# ZoomFloppy_v1_0a.net
KiCad netlist of a schematic drawn in EAGLE
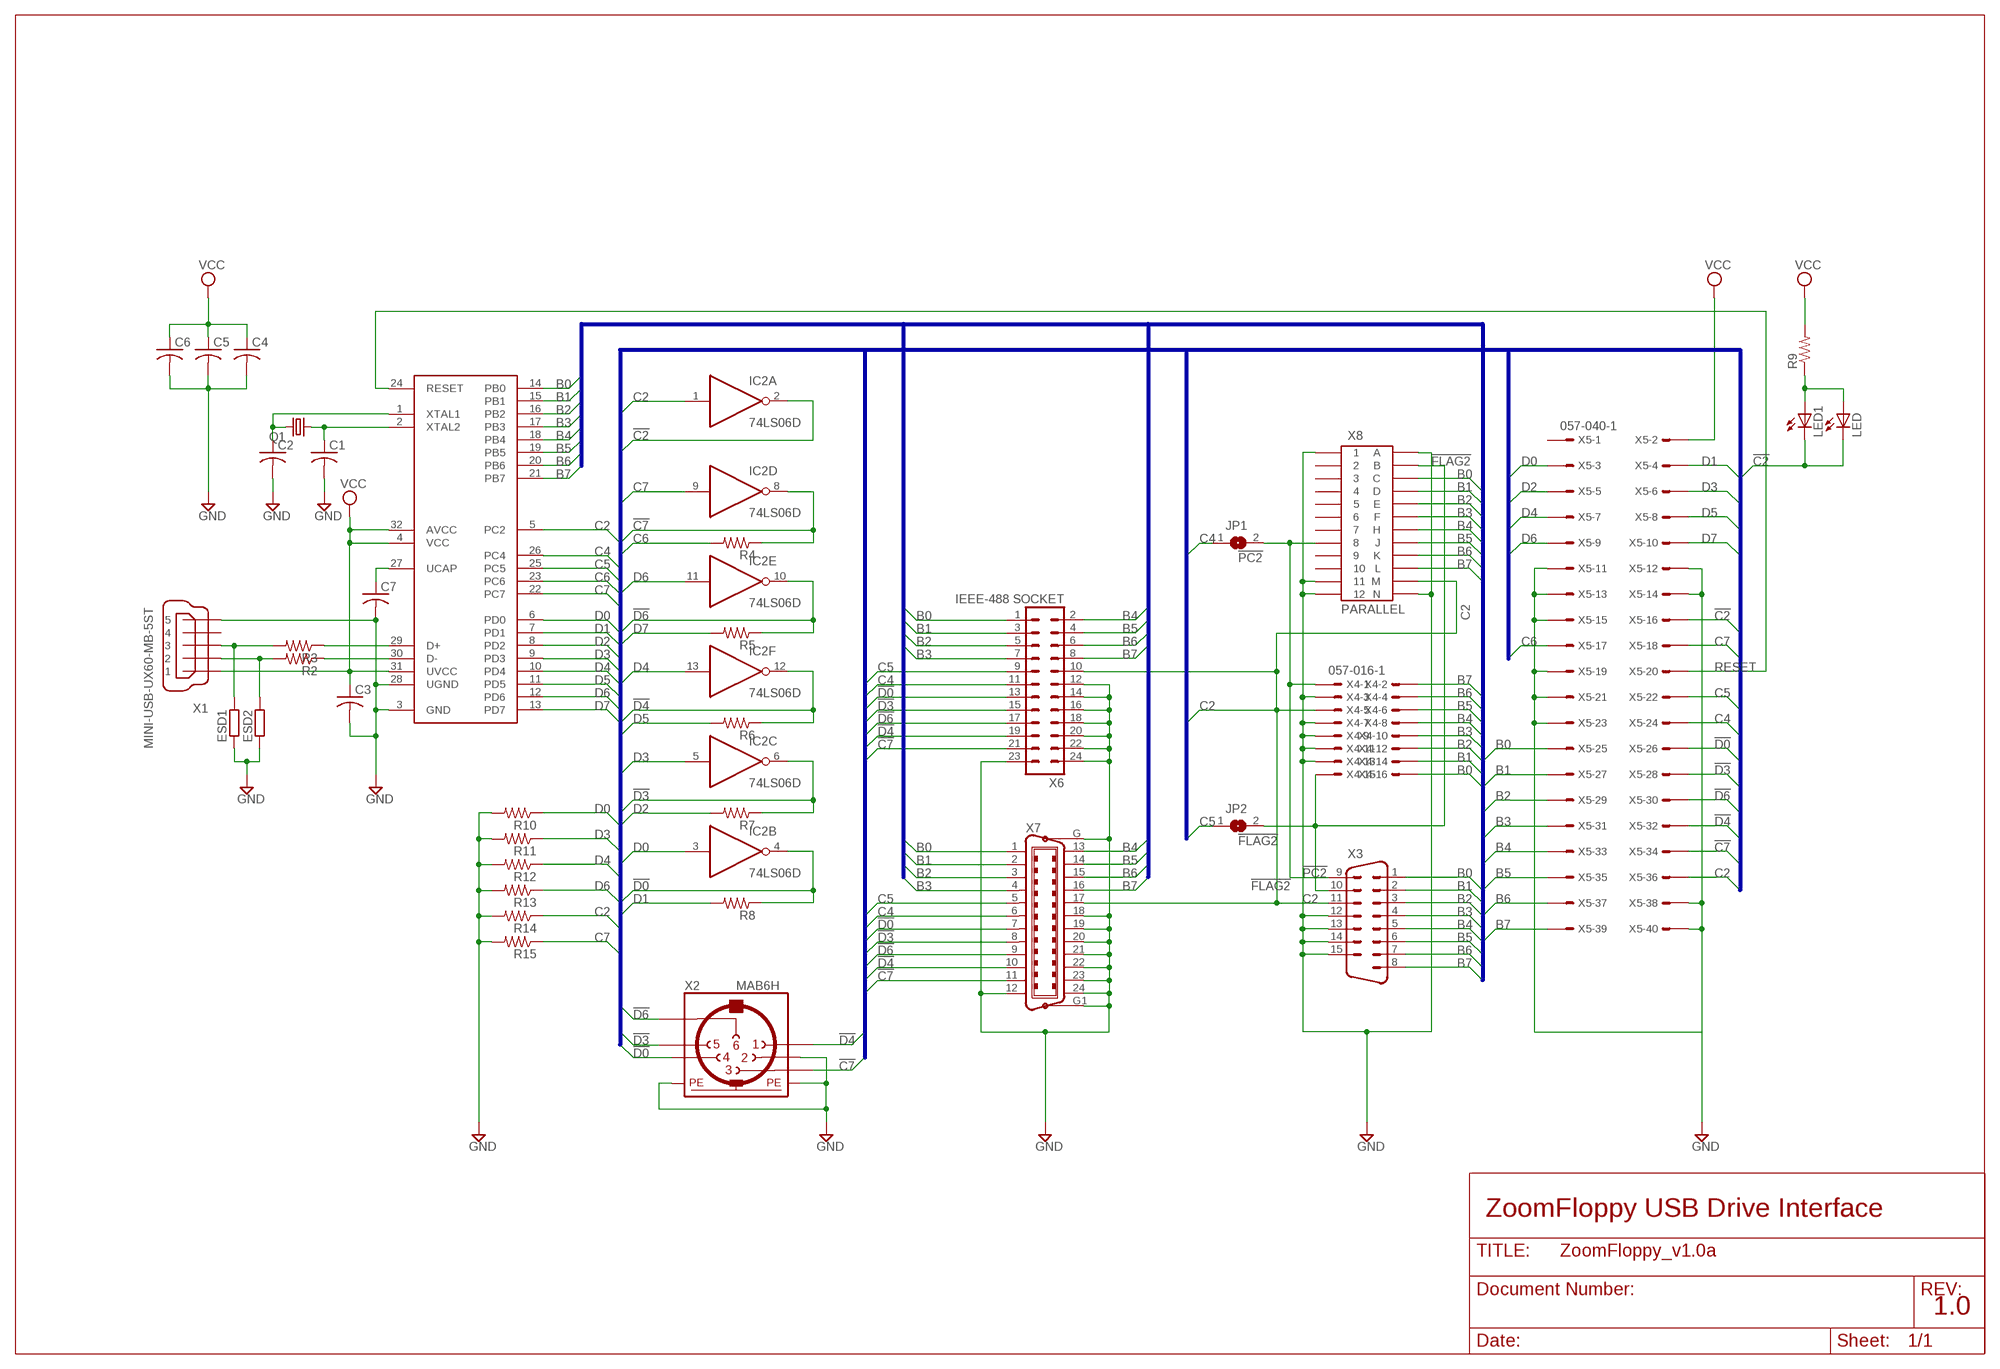
[diagram p0: schematic, sheet 1]

(export (version "E")
  (design (tool "Eeschema 10.0.6"))
  (components
    (comp (ref "C1")
      (value "C-USC0402")
      (footprint "eagle-import:C0402")
      (libsource (lib "eagle-import") (part "C-USC0402"))
    )
    (comp (ref "C2")
      (value "C-USC0402")
      (footprint "eagle-import:C0402")
      (libsource (lib "eagle-import") (part "C-USC0402"))
    )
    (comp (ref "C3")
      (value "C-USC0402")
      (footprint "eagle-import:C0402")
      (libsource (lib "eagle-import") (part "C-USC0402"))
    )
    (comp (ref "C4")
      (value "C-USC0402")
      (footprint "eagle-import:C0402")
      (libsource (lib "eagle-import") (part "C-USC0402"))
    )
    (comp (ref "C5")
      (value "C-USC0402")
      (footprint "eagle-import:C0402")
      (libsource (lib "eagle-import") (part "C-USC0402"))
    )
    (comp (ref "C6")
      (value "C-USC0402")
      (footprint "eagle-import:C0402")
      (libsource (lib "eagle-import") (part "C-USC0402"))
    )
    (comp (ref "C7")
      (value "C-USC0402")
      (footprint "eagle-import:C0402")
      (libsource (lib "eagle-import") (part "C-USC0402"))
    )
    (comp (ref "ESD1")
      (value "R-EU_R0603")
      (footprint "eagle-import:R0603")
      (libsource (lib "eagle-import") (part "R-EU_R0603"))
    )
    (comp (ref "ESD2")
      (value "R-EU_R0603")
      (footprint "eagle-import:R0603")
      (libsource (lib "eagle-import") (part "R-EU_R0603"))
    )
    (comp (ref "IC1")
      (value "ATMEGA32U2")
      (footprint "eagle-import:VQFP32")
      (libsource (lib "eagle-import") (part "AT90USB162"))
    )
    (comp (ref "IC2")
      (value "74LS06D")
      (footprint "eagle-import:SO14")
      (libsource (lib "eagle-import") (part "7406DLS"))
    )
    (comp (ref "JP1") (value "SJ") (footprint "eagle-import:SJ") (libsource (lib "eagle-import") (part "SJ")))
    (comp (ref "JP2") (value "SJ") (footprint "eagle-import:SJ") (libsource (lib "eagle-import") (part "SJ")))
    (comp (ref "LED")
      (value "LED3MM")
      (footprint "eagle-import:LED3MM")
      (libsource (lib "eagle-import") (part "LED3MM"))
    )
    (comp (ref "LED1")
      (value "LEDCHIP-LED0805")
      (footprint "eagle-import:CHIP-LED0805")
      (libsource (lib "eagle-import") (part "LEDCHIP-LED0805"))
    )
    (comp (ref "Q1")
      (value "CRYSTALHC49UP")
      (footprint "eagle-import:HC49UP")
      (libsource (lib "eagle-import") (part "CRYSTALHC49UP"))
    )
    (comp (ref "R2")
      (value "R-US_R0402")
      (footprint "eagle-import:R0402")
      (libsource (lib "eagle-import") (part "R-US_R0402"))
    )
    (comp (ref "R3")
      (value "R-US_R0402")
      (footprint "eagle-import:R0402")
      (libsource (lib "eagle-import") (part "R-US_R0402"))
    )
    (comp (ref "R4")
      (value "R-US_R0402")
      (footprint "eagle-import:R0402")
      (libsource (lib "eagle-import") (part "R-US_R0402"))
    )
    (comp (ref "R5")
      (value "R-US_R0402")
      (footprint "eagle-import:R0402")
      (libsource (lib "eagle-import") (part "R-US_R0402"))
    )
    (comp (ref "R6")
      (value "R-US_R0402")
      (footprint "eagle-import:R0402")
      (libsource (lib "eagle-import") (part "R-US_R0402"))
    )
    (comp (ref "R7")
      (value "R-US_R0402")
      (footprint "eagle-import:R0402")
      (libsource (lib "eagle-import") (part "R-US_R0402"))
    )
    (comp (ref "R8")
      (value "R-US_R0402")
      (footprint "eagle-import:R0402")
      (libsource (lib "eagle-import") (part "R-US_R0402"))
    )
    (comp (ref "R9")
      (value "R-US_R0402")
      (footprint "eagle-import:R0402")
      (libsource (lib "eagle-import") (part "R-US_R0402"))
    )
    (comp (ref "R10")
      (value "R-US_R0402")
      (footprint "eagle-import:R0402")
      (libsource (lib "eagle-import") (part "R-US_R0402"))
    )
    (comp (ref "R11")
      (value "R-US_R0402")
      (footprint "eagle-import:R0402")
      (libsource (lib "eagle-import") (part "R-US_R0402"))
    )
    (comp (ref "R12")
      (value "R-US_R0402")
      (footprint "eagle-import:R0402")
      (libsource (lib "eagle-import") (part "R-US_R0402"))
    )
    (comp (ref "R13")
      (value "R-US_R0402")
      (footprint "eagle-import:R0402")
      (libsource (lib "eagle-import") (part "R-US_R0402"))
    )
    (comp (ref "R14")
      (value "R-US_R0402")
      (footprint "eagle-import:R0402")
      (libsource (lib "eagle-import") (part "R-US_R0402"))
    )
    (comp (ref "R15")
      (value "R-US_R0402")
      (footprint "eagle-import:R0402")
      (libsource (lib "eagle-import") (part "R-US_R0402"))
    )
    (comp (ref "X1")
      (value "MINI-USB-UX60-MB-5ST")
      (footprint "eagle-import:UX60-MB-5ST")
      (libsource (lib "eagle-import") (part "MINI-USB-UX60-MB-5ST"))
    )
    (comp (ref "X2")
      (value "MAB6H")
      (footprint "eagle-import:MAB6H")
      (libsource (lib "eagle-import") (part "MAB6H"))
    )
    (comp (ref "X3")
      (value "M15-182")
      (footprint "eagle-import:182-015-MALE")
      (libsource (lib "eagle-import") (part "M15-182"))
    )
    (comp (ref "X4")
      (value "057-016-1")
      (footprint "eagle-import:057-016-1")
      (libsource (lib "eagle-import") (part "057-016-1"))
    )
    (comp (ref "X5")
      (value "057-040-1")
      (footprint "eagle-import:057-040-1")
      (libsource (lib "eagle-import") (part "057-040-1"))
    )
    (comp (ref "X6")
      (value "IEEE-488 SOCKET")
      (footprint "eagle-import:MA12-2")
      (libsource (lib "eagle-import") (part "MA12-2"))
    )
    (comp (ref "X7")
      (value "C24HP")
      (footprint "eagle-import:24HP")
      (libsource (lib "eagle-import") (part "C24HP"))
    )
    (comp (ref "X8")
      (value "PARALLEL")
      (footprint "eagle-import:MA-24")
      (libsource (lib "eagle-import") (part "MA-24"))
    )
  )
  (nets
    (net (code "1") (name "/B0") (class "Default")
      (node (ref "IC1") (pin "14") (pinfunction "PB0_14") (pintype "bidirectional"))
      (node (ref "X3") (pin "1") (pinfunction "1_1") (pintype "passive"))
      (node (ref "X4") (pin "16") (pinfunction "S_16") (pintype "passive"))
      (node (ref "X5") (pin "25") (pinfunction "S_25") (pintype "passive"))
      (node (ref "X6") (pin "1") (pinfunction "1_1") (pintype "passive"))
      (node (ref "X7") (pin "1") (pinfunction "1_1") (pintype "passive"))
      (node (ref "X8") (pin "C") (pinfunction "C_C") (pintype "passive"))
    )
    (net (code "2") (name "/B1") (class "Default")
      (node (ref "IC1") (pin "15") (pinfunction "PB1_15") (pintype "bidirectional"))
      (node (ref "X3") (pin "2") (pinfunction "2_2") (pintype "passive"))
      (node (ref "X4") (pin "14") (pinfunction "S_14") (pintype "passive"))
      (node (ref "X5") (pin "27") (pinfunction "S_27") (pintype "passive"))
      (node (ref "X6") (pin "3") (pinfunction "3_3") (pintype "passive"))
      (node (ref "X7") (pin "2") (pinfunction "2_2") (pintype "passive"))
      (node (ref "X8") (pin "D") (pinfunction "D_D") (pintype "passive"))
    )
    (net (code "3") (name "/B2") (class "Default")
      (node (ref "IC1") (pin "16") (pinfunction "PB2_16") (pintype "bidirectional"))
      (node (ref "X3") (pin "3") (pinfunction "3_3") (pintype "passive"))
      (node (ref "X4") (pin "12") (pinfunction "S_12") (pintype "passive"))
      (node (ref "X5") (pin "29") (pinfunction "S_29") (pintype "passive"))
      (node (ref "X6") (pin "5") (pinfunction "5_5") (pintype "passive"))
      (node (ref "X7") (pin "3") (pinfunction "3_3") (pintype "passive"))
      (node (ref "X8") (pin "E") (pinfunction "E_E") (pintype "passive"))
    )
    (net (code "4") (name "/B3") (class "Default")
      (node (ref "IC1") (pin "17") (pinfunction "PB3_17") (pintype "bidirectional"))
      (node (ref "X3") (pin "4") (pinfunction "4_4") (pintype "passive"))
      (node (ref "X4") (pin "10") (pinfunction "S_10") (pintype "passive"))
      (node (ref "X5") (pin "31") (pinfunction "S_31") (pintype "passive"))
      (node (ref "X6") (pin "7") (pinfunction "7_7") (pintype "passive"))
      (node (ref "X7") (pin "4") (pinfunction "4_4") (pintype "passive"))
      (node (ref "X8") (pin "F") (pinfunction "F_F") (pintype "passive"))
    )
    (net (code "5") (name "/B4") (class "Default")
      (node (ref "IC1") (pin "18") (pinfunction "PB4_18") (pintype "bidirectional"))
      (node (ref "X3") (pin "5") (pinfunction "5_5") (pintype "passive"))
      (node (ref "X4") (pin "8") (pinfunction "S_8") (pintype "passive"))
      (node (ref "X5") (pin "33") (pinfunction "S_33") (pintype "passive"))
      (node (ref "X6") (pin "2") (pinfunction "2_2") (pintype "passive"))
      (node (ref "X7") (pin "13") (pinfunction "13_13") (pintype "passive"))
      (node (ref "X8") (pin "H") (pinfunction "H_H") (pintype "passive"))
    )
    (net (code "6") (name "/B5") (class "Default")
      (node (ref "IC1") (pin "19") (pinfunction "PB5_19") (pintype "bidirectional"))
      (node (ref "X3") (pin "6") (pinfunction "6_6") (pintype "passive"))
      (node (ref "X4") (pin "6") (pinfunction "S_6") (pintype "passive"))
      (node (ref "X5") (pin "35") (pinfunction "S_35") (pintype "passive"))
      (node (ref "X6") (pin "4") (pinfunction "4_4") (pintype "passive"))
      (node (ref "X7") (pin "14") (pinfunction "14_14") (pintype "passive"))
      (node (ref "X8") (pin "J") (pinfunction "J_J") (pintype "passive"))
    )
    (net (code "7") (name "/B6") (class "Default")
      (node (ref "IC1") (pin "20") (pinfunction "PB6_20") (pintype "bidirectional"))
      (node (ref "X3") (pin "7") (pinfunction "7_7") (pintype "passive"))
      (node (ref "X4") (pin "4") (pinfunction "S_4") (pintype "passive"))
      (node (ref "X5") (pin "37") (pinfunction "S_37") (pintype "passive"))
      (node (ref "X6") (pin "6") (pinfunction "6_6") (pintype "passive"))
      (node (ref "X7") (pin "15") (pinfunction "15_15") (pintype "passive"))
      (node (ref "X8") (pin "K") (pinfunction "K_K") (pintype "passive"))
    )
    (net (code "8") (name "/B7") (class "Default")
      (node (ref "IC1") (pin "21") (pinfunction "PB7_21") (pintype "bidirectional"))
      (node (ref "X3") (pin "8") (pinfunction "8_8") (pintype "passive"))
      (node (ref "X4") (pin "2") (pinfunction "S_2") (pintype "passive"))
      (node (ref "X5") (pin "39") (pinfunction "S_39") (pintype "passive"))
      (node (ref "X6") (pin "8") (pinfunction "8_8") (pintype "passive"))
      (node (ref "X7") (pin "16") (pinfunction "16_16") (pintype "passive"))
      (node (ref "X8") (pin "L") (pinfunction "L_L") (pintype "passive"))
    )
    (net (code "9") (name "/C2") (class "Default")
      (node (ref "IC1") (pin "5") (pinfunction "PC2_5") (pintype "bidirectional"))
      (node (ref "IC2") (pin "1") (pinfunction "I_1") (pintype "input"))
      (node (ref "R14") (pin "1") (pinfunction "1_1") (pintype "passive"))
      (node (ref "X3") (pin "11") (pinfunction "11_11") (pintype "passive"))
      (node (ref "X4") (pin "5") (pinfunction "S_5") (pintype "passive"))
      (node (ref "X5") (pin "36") (pinfunction "S_36") (pintype "passive"))
      (node (ref "X6") (pin "10") (pinfunction "10_10") (pintype "passive"))
      (node (ref "X7") (pin "17") (pinfunction "17_17") (pintype "passive"))
      (node (ref "X8") (pin "M") (pinfunction "M_M") (pintype "passive"))
    )
    (net (code "10") (name "/C4") (class "Default")
      (node (ref "IC1") (pin "26") (pinfunction "PC4_26") (pintype "bidirectional"))
      (node (ref "JP1") (pin "1") (pinfunction "1_1") (pintype "passive"))
      (node (ref "X5") (pin "24") (pinfunction "S_24") (pintype "passive"))
      (node (ref "X6") (pin "11") (pinfunction "11_11") (pintype "passive"))
      (node (ref "X7") (pin "6") (pinfunction "6_6") (pintype "passive"))
    )
    (net (code "11") (name "/C5") (class "Default")
      (node (ref "IC1") (pin "25") (pinfunction "PC5_25") (pintype "bidirectional"))
      (node (ref "JP2") (pin "1") (pinfunction "1_1") (pintype "passive"))
      (node (ref "X5") (pin "22") (pinfunction "S_22") (pintype "passive"))
      (node (ref "X6") (pin "9") (pinfunction "9_9") (pintype "passive"))
      (node (ref "X7") (pin "5") (pinfunction "5_5") (pintype "passive"))
    )
    (net (code "12") (name "/C6") (class "Default")
      (node (ref "IC1") (pin "23") (pinfunction "PC6_23") (pintype "bidirectional"))
      (node (ref "R4") (pin "2") (pinfunction "2_2") (pintype "passive"))
      (node (ref "X5") (pin "17") (pinfunction "S_17") (pintype "passive"))
    )
    (net (code "13") (name "/C7") (class "Default")
      (node (ref "IC1") (pin "22") (pinfunction "PC7_22") (pintype "bidirectional"))
      (node (ref "IC2") (pin "9") (pinfunction "I_9") (pintype "input"))
      (node (ref "R15") (pin "1") (pinfunction "1_1") (pintype "passive"))
      (node (ref "X5") (pin "18") (pinfunction "S_18") (pintype "passive"))
    )
    (net (code "14") (name "/D0") (class "Default")
      (node (ref "IC1") (pin "6") (pinfunction "PD0_6") (pintype "bidirectional"))
      (node (ref "IC2") (pin "3") (pinfunction "I_3") (pintype "input"))
      (node (ref "R10") (pin "1") (pinfunction "1_1") (pintype "passive"))
      (node (ref "X5") (pin "3") (pinfunction "S_3") (pintype "passive"))
    )
    (net (code "15") (name "/D1") (class "Default")
      (node (ref "IC1") (pin "7") (pinfunction "PD1_7") (pintype "bidirectional"))
      (node (ref "R8") (pin "2") (pinfunction "2_2") (pintype "passive"))
      (node (ref "X5") (pin "4") (pinfunction "S_4") (pintype "passive"))
    )
    (net (code "16") (name "/D2") (class "Default")
      (node (ref "IC1") (pin "8") (pinfunction "PD2_8") (pintype "bidirectional"))
      (node (ref "R7") (pin "2") (pinfunction "2_2") (pintype "passive"))
      (node (ref "X5") (pin "5") (pinfunction "S_5") (pintype "passive"))
    )
    (net (code "17") (name "/D3") (class "Default")
      (node (ref "IC1") (pin "9") (pinfunction "PD3_9") (pintype "bidirectional"))
      (node (ref "IC2") (pin "5") (pinfunction "I_5") (pintype "input"))
      (node (ref "R11") (pin "1") (pinfunction "1_1") (pintype "passive"))
      (node (ref "X5") (pin "6") (pinfunction "S_6") (pintype "passive"))
    )
    (net (code "18") (name "/D4") (class "Default")
      (node (ref "IC1") (pin "10") (pinfunction "PD4_10") (pintype "bidirectional"))
      (node (ref "IC2") (pin "13") (pinfunction "I_13") (pintype "input"))
      (node (ref "R12") (pin "1") (pinfunction "1_1") (pintype "passive"))
      (node (ref "X5") (pin "7") (pinfunction "S_7") (pintype "passive"))
    )
    (net (code "19") (name "/D5") (class "Default")
      (node (ref "IC1") (pin "11") (pinfunction "PD5_11") (pintype "bidirectional"))
      (node (ref "R6") (pin "2") (pinfunction "2_2") (pintype "passive"))
      (node (ref "X5") (pin "8") (pinfunction "S_8") (pintype "passive"))
    )
    (net (code "20") (name "/D6") (class "Default")
      (node (ref "IC1") (pin "12") (pinfunction "PD6_12") (pintype "bidirectional"))
      (node (ref "IC2") (pin "11") (pinfunction "I_11") (pintype "input"))
      (node (ref "R13") (pin "1") (pinfunction "1_1") (pintype "passive"))
      (node (ref "X5") (pin "9") (pinfunction "S_9") (pintype "passive"))
    )
    (net (code "21") (name "/D7") (class "Default")
      (node (ref "IC1") (pin "13") (pinfunction "PD7_13") (pintype "bidirectional"))
      (node (ref "R5") (pin "2") (pinfunction "2_2") (pintype "passive"))
      (node (ref "X5") (pin "10") (pinfunction "S_10") (pintype "passive"))
    )
    (net (code "22") (name "/RESET") (class "Default")
      (node (ref "IC1") (pin "24") (pinfunction "RESET_24") (pintype "bidirectional"))
      (node (ref "X5") (pin "20") (pinfunction "S_20") (pintype "passive"))
    )
    (net (code "23") (name "/~{C2}") (class "Default")
      (node (ref "IC2") (pin "2") (pinfunction "O_2") (pintype "open_collector"))
      (node (ref "LED") (pin "K") (pinfunction "C_K") (pintype "passive"))
      (node (ref "LED1") (pin "C") (pinfunction "C_C") (pintype "passive"))
      (node (ref "X5") (pin "16") (pinfunction "S_16") (pintype "passive"))
    )
    (net (code "24") (name "/~{C7}") (class "Default")
      (node (ref "IC2") (pin "8") (pinfunction "O_8") (pintype "open_collector"))
      (node (ref "R4") (pin "1") (pinfunction "1_1") (pintype "passive"))
      (node (ref "X2") (pin "3") (pinfunction "3_3") (pintype "passive"))
      (node (ref "X5") (pin "34") (pinfunction "S_34") (pintype "passive"))
      (node (ref "X6") (pin "21") (pinfunction "21_21") (pintype "passive"))
      (node (ref "X7") (pin "11") (pinfunction "11_11") (pintype "passive"))
    )
    (net (code "25") (name "/~{D0}") (class "Default")
      (node (ref "IC2") (pin "4") (pinfunction "O_4") (pintype "open_collector"))
      (node (ref "R8") (pin "1") (pinfunction "1_1") (pintype "passive"))
      (node (ref "X2") (pin "4") (pinfunction "4_4") (pintype "passive"))
      (node (ref "X5") (pin "26") (pinfunction "S_26") (pintype "passive"))
      (node (ref "X6") (pin "13") (pinfunction "13_13") (pintype "passive"))
      (node (ref "X7") (pin "7") (pinfunction "7_7") (pintype "passive"))
    )
    (net (code "26") (name "/~{D3}") (class "Default")
      (node (ref "IC2") (pin "6") (pinfunction "O_6") (pintype "open_collector"))
      (node (ref "R7") (pin "1") (pinfunction "1_1") (pintype "passive"))
      (node (ref "X2") (pin "5") (pinfunction "5_5") (pintype "passive"))
      (node (ref "X5") (pin "28") (pinfunction "S_28") (pintype "passive"))
      (node (ref "X6") (pin "15") (pinfunction "15_15") (pintype "passive"))
      (node (ref "X7") (pin "8") (pinfunction "8_8") (pintype "passive"))
    )
    (net (code "27") (name "/~{D4}") (class "Default")
      (node (ref "IC2") (pin "12") (pinfunction "O_12") (pintype "open_collector"))
      (node (ref "R6") (pin "1") (pinfunction "1_1") (pintype "passive"))
      (node (ref "X2") (pin "1") (pinfunction "1_1") (pintype "passive"))
      (node (ref "X5") (pin "32") (pinfunction "S_32") (pintype "passive"))
      (node (ref "X6") (pin "19") (pinfunction "19_19") (pintype "passive"))
      (node (ref "X7") (pin "10") (pinfunction "10_10") (pintype "passive"))
    )
    (net (code "28") (name "/~{D6}") (class "Default")
      (node (ref "IC2") (pin "10") (pinfunction "O_10") (pintype "open_collector"))
      (node (ref "R5") (pin "1") (pinfunction "1_1") (pintype "passive"))
      (node (ref "X2") (pin "6") (pinfunction "6_6") (pintype "passive"))
      (node (ref "X5") (pin "30") (pinfunction "S_30") (pintype "passive"))
      (node (ref "X6") (pin "17") (pinfunction "17_17") (pintype "passive"))
      (node (ref "X7") (pin "9") (pinfunction "9_9") (pintype "passive"))
    )
    (net (code "29") (name "/~{FLAG2}") (class "Default")
      (node (ref "JP2") (pin "2") (pinfunction "2_2") (pintype "passive"))
      (node (ref "X3") (pin "10") (pinfunction "10_10") (pintype "passive"))
      (node (ref "X4") (pin "15") (pinfunction "S_15") (pintype "passive"))
      (node (ref "X8") (pin "B") (pinfunction "B_B") (pintype "passive"))
    )
    (net (code "30") (name "/~{PC2}") (class "Default")
      (node (ref "JP1") (pin "2") (pinfunction "2_2") (pintype "passive"))
      (node (ref "X3") (pin "9") (pinfunction "9_9") (pintype "passive"))
      (node (ref "X4") (pin "1") (pinfunction "S_1") (pintype "passive"))
      (node (ref "X8") (pin "8") (pinfunction "8_8") (pintype "passive"))
    )
    (net (code "31") (name "GND") (class "Default")
      (node (ref "C1") (pin "2") (pinfunction "2_2") (pintype "passive"))
      (node (ref "C2") (pin "2") (pinfunction "2_2") (pintype "passive"))
      (node (ref "C3") (pin "2") (pinfunction "2_2") (pintype "passive"))
      (node (ref "C4") (pin "2") (pinfunction "2_2") (pintype "passive"))
      (node (ref "C5") (pin "2") (pinfunction "2_2") (pintype "passive"))
      (node (ref "C6") (pin "2") (pinfunction "2_2") (pintype "passive"))
      (node (ref "C7") (pin "2") (pinfunction "2_2") (pintype "passive"))
      (node (ref "ESD1") (pin "1") (pinfunction "1_1") (pintype "passive"))
      (node (ref "ESD2") (pin "1") (pinfunction "1_1") (pintype "passive"))
      (node (ref "IC1") (pin "28") (pinfunction "UGND_28") (pintype "bidirectional"))
      (node (ref "IC1") (pin "3") (pinfunction "GND_3") (pintype "power_in"))
      (node (ref "R10") (pin "2") (pinfunction "2_2") (pintype "passive"))
      (node (ref "R11") (pin "2") (pinfunction "2_2") (pintype "passive"))
      (node (ref "R12") (pin "2") (pinfunction "2_2") (pintype "passive"))
      (node (ref "R13") (pin "2") (pinfunction "2_2") (pintype "passive"))
      (node (ref "R14") (pin "2") (pinfunction "2_2") (pintype "passive"))
      (node (ref "R15") (pin "2") (pinfunction "2_2") (pintype "passive"))
      (node (ref "X1") (pin "5") (pinfunction "5_5") (pintype "input"))
      (node (ref "X2") (pin "2") (pinfunction "2_2") (pintype "passive"))
      (node (ref "X2") (pin "PE") (pinfunction "PE_PE") (pintype "power_in"))
      (node (ref "X2") (pin "PE@") (pinfunction "PE_PE@") (pintype "power_in"))
      (node (ref "X3") (pin "12") (pinfunction "12_12") (pintype "passive"))
      (node (ref "X3") (pin "13") (pinfunction "13_13") (pintype "passive"))
      (node (ref "X3") (pin "14") (pinfunction "14_14") (pintype "passive"))
      (node (ref "X3") (pin "15") (pinfunction "15_15") (pintype "passive"))
      (node (ref "X4") (pin "11") (pinfunction "S_11") (pintype "passive"))
      (node (ref "X4") (pin "13") (pinfunction "S_13") (pintype "passive"))
      (node (ref "X4") (pin "3") (pinfunction "S_3") (pintype "passive"))
      (node (ref "X4") (pin "7") (pinfunction "S_7") (pintype "passive"))
      (node (ref "X4") (pin "9") (pinfunction "S_9") (pintype "passive"))
      (node (ref "X5") (pin "11") (pinfunction "S_11") (pintype "passive"))
      (node (ref "X5") (pin "12") (pinfunction "S_12") (pintype "passive"))
      (node (ref "X5") (pin "13") (pinfunction "S_13") (pintype "passive"))
      (node (ref "X5") (pin "14") (pinfunction "S_14") (pintype "passive"))
      (node (ref "X5") (pin "15") (pinfunction "S_15") (pintype "passive"))
      (node (ref "X5") (pin "19") (pinfunction "S_19") (pintype "passive"))
      (node (ref "X5") (pin "21") (pinfunction "S_21") (pintype "passive"))
      (node (ref "X5") (pin "23") (pinfunction "S_23") (pintype "passive"))
      (node (ref "X5") (pin "38") (pinfunction "S_38") (pintype "passive"))
      (node (ref "X5") (pin "40") (pinfunction "S_40") (pintype "passive"))
      (node (ref "X6") (pin "12") (pinfunction "12_12") (pintype "passive"))
      (node (ref "X6") (pin "14") (pinfunction "14_14") (pintype "passive"))
      (node (ref "X6") (pin "16") (pinfunction "16_16") (pintype "passive"))
      (node (ref "X6") (pin "18") (pinfunction "18_18") (pintype "passive"))
      (node (ref "X6") (pin "20") (pinfunction "20_20") (pintype "passive"))
      (node (ref "X6") (pin "22") (pinfunction "22_22") (pintype "passive"))
      (node (ref "X6") (pin "23") (pinfunction "23_23") (pintype "passive"))
      (node (ref "X6") (pin "24") (pinfunction "24_24") (pintype "passive"))
      (node (ref "X7") (pin "12") (pinfunction "12_12") (pintype "passive"))
      (node (ref "X7") (pin "18") (pinfunction "18_18") (pintype "passive"))
      (node (ref "X7") (pin "19") (pinfunction "19_19") (pintype "passive"))
      (node (ref "X7") (pin "20") (pinfunction "20_20") (pintype "passive"))
      (node (ref "X7") (pin "21") (pinfunction "21_21") (pintype "passive"))
      (node (ref "X7") (pin "22") (pinfunction "22_22") (pintype "passive"))
      (node (ref "X7") (pin "23") (pinfunction "23_23") (pintype "passive"))
      (node (ref "X7") (pin "24") (pinfunction "24_24") (pintype "passive"))
      (node (ref "X7") (pin "G") (pinfunction "G_G") (pintype "passive"))
      (node (ref "X7") (pin "G1") (pinfunction "G1_G1") (pintype "passive"))
      (node (ref "X8") (pin "1") (pinfunction "1_1") (pintype "passive"))
      (node (ref "X8") (pin "11") (pinfunction "11_11") (pintype "passive"))
      (node (ref "X8") (pin "12") (pinfunction "12_12") (pintype "passive"))
      (node (ref "X8") (pin "A") (pinfunction "A_A") (pintype "passive"))
      (node (ref "X8") (pin "N") (pinfunction "N_N") (pintype "passive"))
    )
    (net (code "32") (name "Net-(ESD1-Pad2)") (class "Default")
      (node (ref "ESD1") (pin "2") (pinfunction "2_2") (pintype "passive"))
      (node (ref "R3") (pin "2") (pinfunction "2_2") (pintype "passive"))
      (node (ref "X1") (pin "3") (pinfunction "3_3") (pintype "input"))
    )
    (net (code "33") (name "Net-(ESD2-Pad2)") (class "Default")
      (node (ref "ESD2") (pin "2") (pinfunction "2_2") (pintype "passive"))
      (node (ref "R2") (pin "2") (pinfunction "2_2") (pintype "passive"))
      (node (ref "X1") (pin "2") (pinfunction "2_2") (pintype "input"))
    )
    (net (code "34") (name "Net-(IC1-D+)") (class "Default")
      (node (ref "IC1") (pin "29") (pinfunction "D+_29") (pintype "bidirectional"))
      (node (ref "R3") (pin "1") (pinfunction "1_1") (pintype "passive"))
    )
    (net (code "35") (name "Net-(IC1-D-)") (class "Default")
      (node (ref "IC1") (pin "30") (pinfunction "D-_30") (pintype "bidirectional"))
      (node (ref "R2") (pin "1") (pinfunction "1_1") (pintype "passive"))
    )
    (net (code "36") (name "Net-(IC1-UCAP)") (class "Default")
      (node (ref "C7") (pin "1") (pinfunction "1_1") (pintype "passive"))
      (node (ref "IC1") (pin "27") (pinfunction "UCAP_27") (pintype "bidirectional"))
    )
    (net (code "37") (name "Net-(IC1-XTAL1)") (class "Default")
      (node (ref "C2") (pin "1") (pinfunction "1_1") (pintype "passive"))
      (node (ref "IC1") (pin "1") (pinfunction "XTAL1_1") (pintype "bidirectional"))
      (node (ref "Q1") (pin "2") (pinfunction "2_2") (pintype "passive"))
    )
    (net (code "38") (name "Net-(IC1-XTAL2)") (class "Default")
      (node (ref "C1") (pin "1") (pinfunction "1_1") (pintype "passive"))
      (node (ref "IC1") (pin "2") (pinfunction "XTAL2_2") (pintype "bidirectional"))
      (node (ref "Q1") (pin "1") (pinfunction "1_1") (pintype "passive"))
    )
    (net (code "39") (name "Net-(LED-PadA)") (class "Default")
      (node (ref "LED") (pin "A") (pinfunction "A_A") (pintype "passive"))
      (node (ref "LED1") (pin "A") (pinfunction "A_A") (pintype "passive"))
      (node (ref "R9") (pin "1") (pinfunction "1_1") (pintype "passive"))
    )
    (net (code "40") (name "VCC") (class "Default")
      (node (ref "C3") (pin "1") (pinfunction "1_1") (pintype "passive"))
      (node (ref "C4") (pin "1") (pinfunction "1_1") (pintype "passive"))
      (node (ref "C5") (pin "1") (pinfunction "1_1") (pintype "passive"))
      (node (ref "C6") (pin "1") (pinfunction "1_1") (pintype "passive"))
      (node (ref "IC1") (pin "31") (pinfunction "UVCC_31") (pintype "bidirectional"))
      (node (ref "IC1") (pin "32") (pinfunction "AVCC_32") (pintype "bidirectional"))
      (node (ref "IC1") (pin "4") (pinfunction "VCC_4") (pintype "power_in"))
      (node (ref "R9") (pin "2") (pinfunction "2_2") (pintype "passive"))
      (node (ref "X1") (pin "1") (pinfunction "1_1") (pintype "input"))
      (node (ref "X5") (pin "2") (pinfunction "S_2") (pintype "passive"))
    )
    (net (code "41") (name "unconnected-(X1-Pad4)") (class "Default")
      (node (ref "X1") (pin "4") (pinfunction "4_4") (pintype "input"))
    )
    (net (code "42") (name "unconnected-(X5A-S-Pad1)") (class "Default")
      (node (ref "X5") (pin "1") (pinfunction "S_1") (pintype "passive"))
    )
    (net (code "43") (name "unconnected-(X8-Pad2)") (class "Default")
      (node (ref "X8") (pin "2") (pinfunction "2_2") (pintype "passive"))
    )
    (net (code "44") (name "unconnected-(X8-Pad3)") (class "Default")
      (node (ref "X8") (pin "3") (pinfunction "3_3") (pintype "passive"))
    )
    (net (code "45") (name "unconnected-(X8-Pad4)") (class "Default")
      (node (ref "X8") (pin "4") (pinfunction "4_4") (pintype "passive"))
    )
    (net (code "46") (name "unconnected-(X8-Pad5)") (class "Default")
      (node (ref "X8") (pin "5") (pinfunction "5_5") (pintype "passive"))
    )
    (net (code "47") (name "unconnected-(X8-Pad6)") (class "Default")
      (node (ref "X8") (pin "6") (pinfunction "6_6") (pintype "passive"))
    )
    (net (code "48") (name "unconnected-(X8-Pad7)") (class "Default")
      (node (ref "X8") (pin "7") (pinfunction "7_7") (pintype "passive"))
    )
    (net (code "49") (name "unconnected-(X8-Pad9)") (class "Default")
      (node (ref "X8") (pin "9") (pinfunction "9_9") (pintype "passive"))
    )
    (net (code "50") (name "unconnected-(X8-Pad10)") (class "Default")
      (node (ref "X8") (pin "10") (pinfunction "10_10") (pintype "passive"))
    )
  )
)
